# schematics.net
KiCad netlist of a schematic drawn in EasyEDA
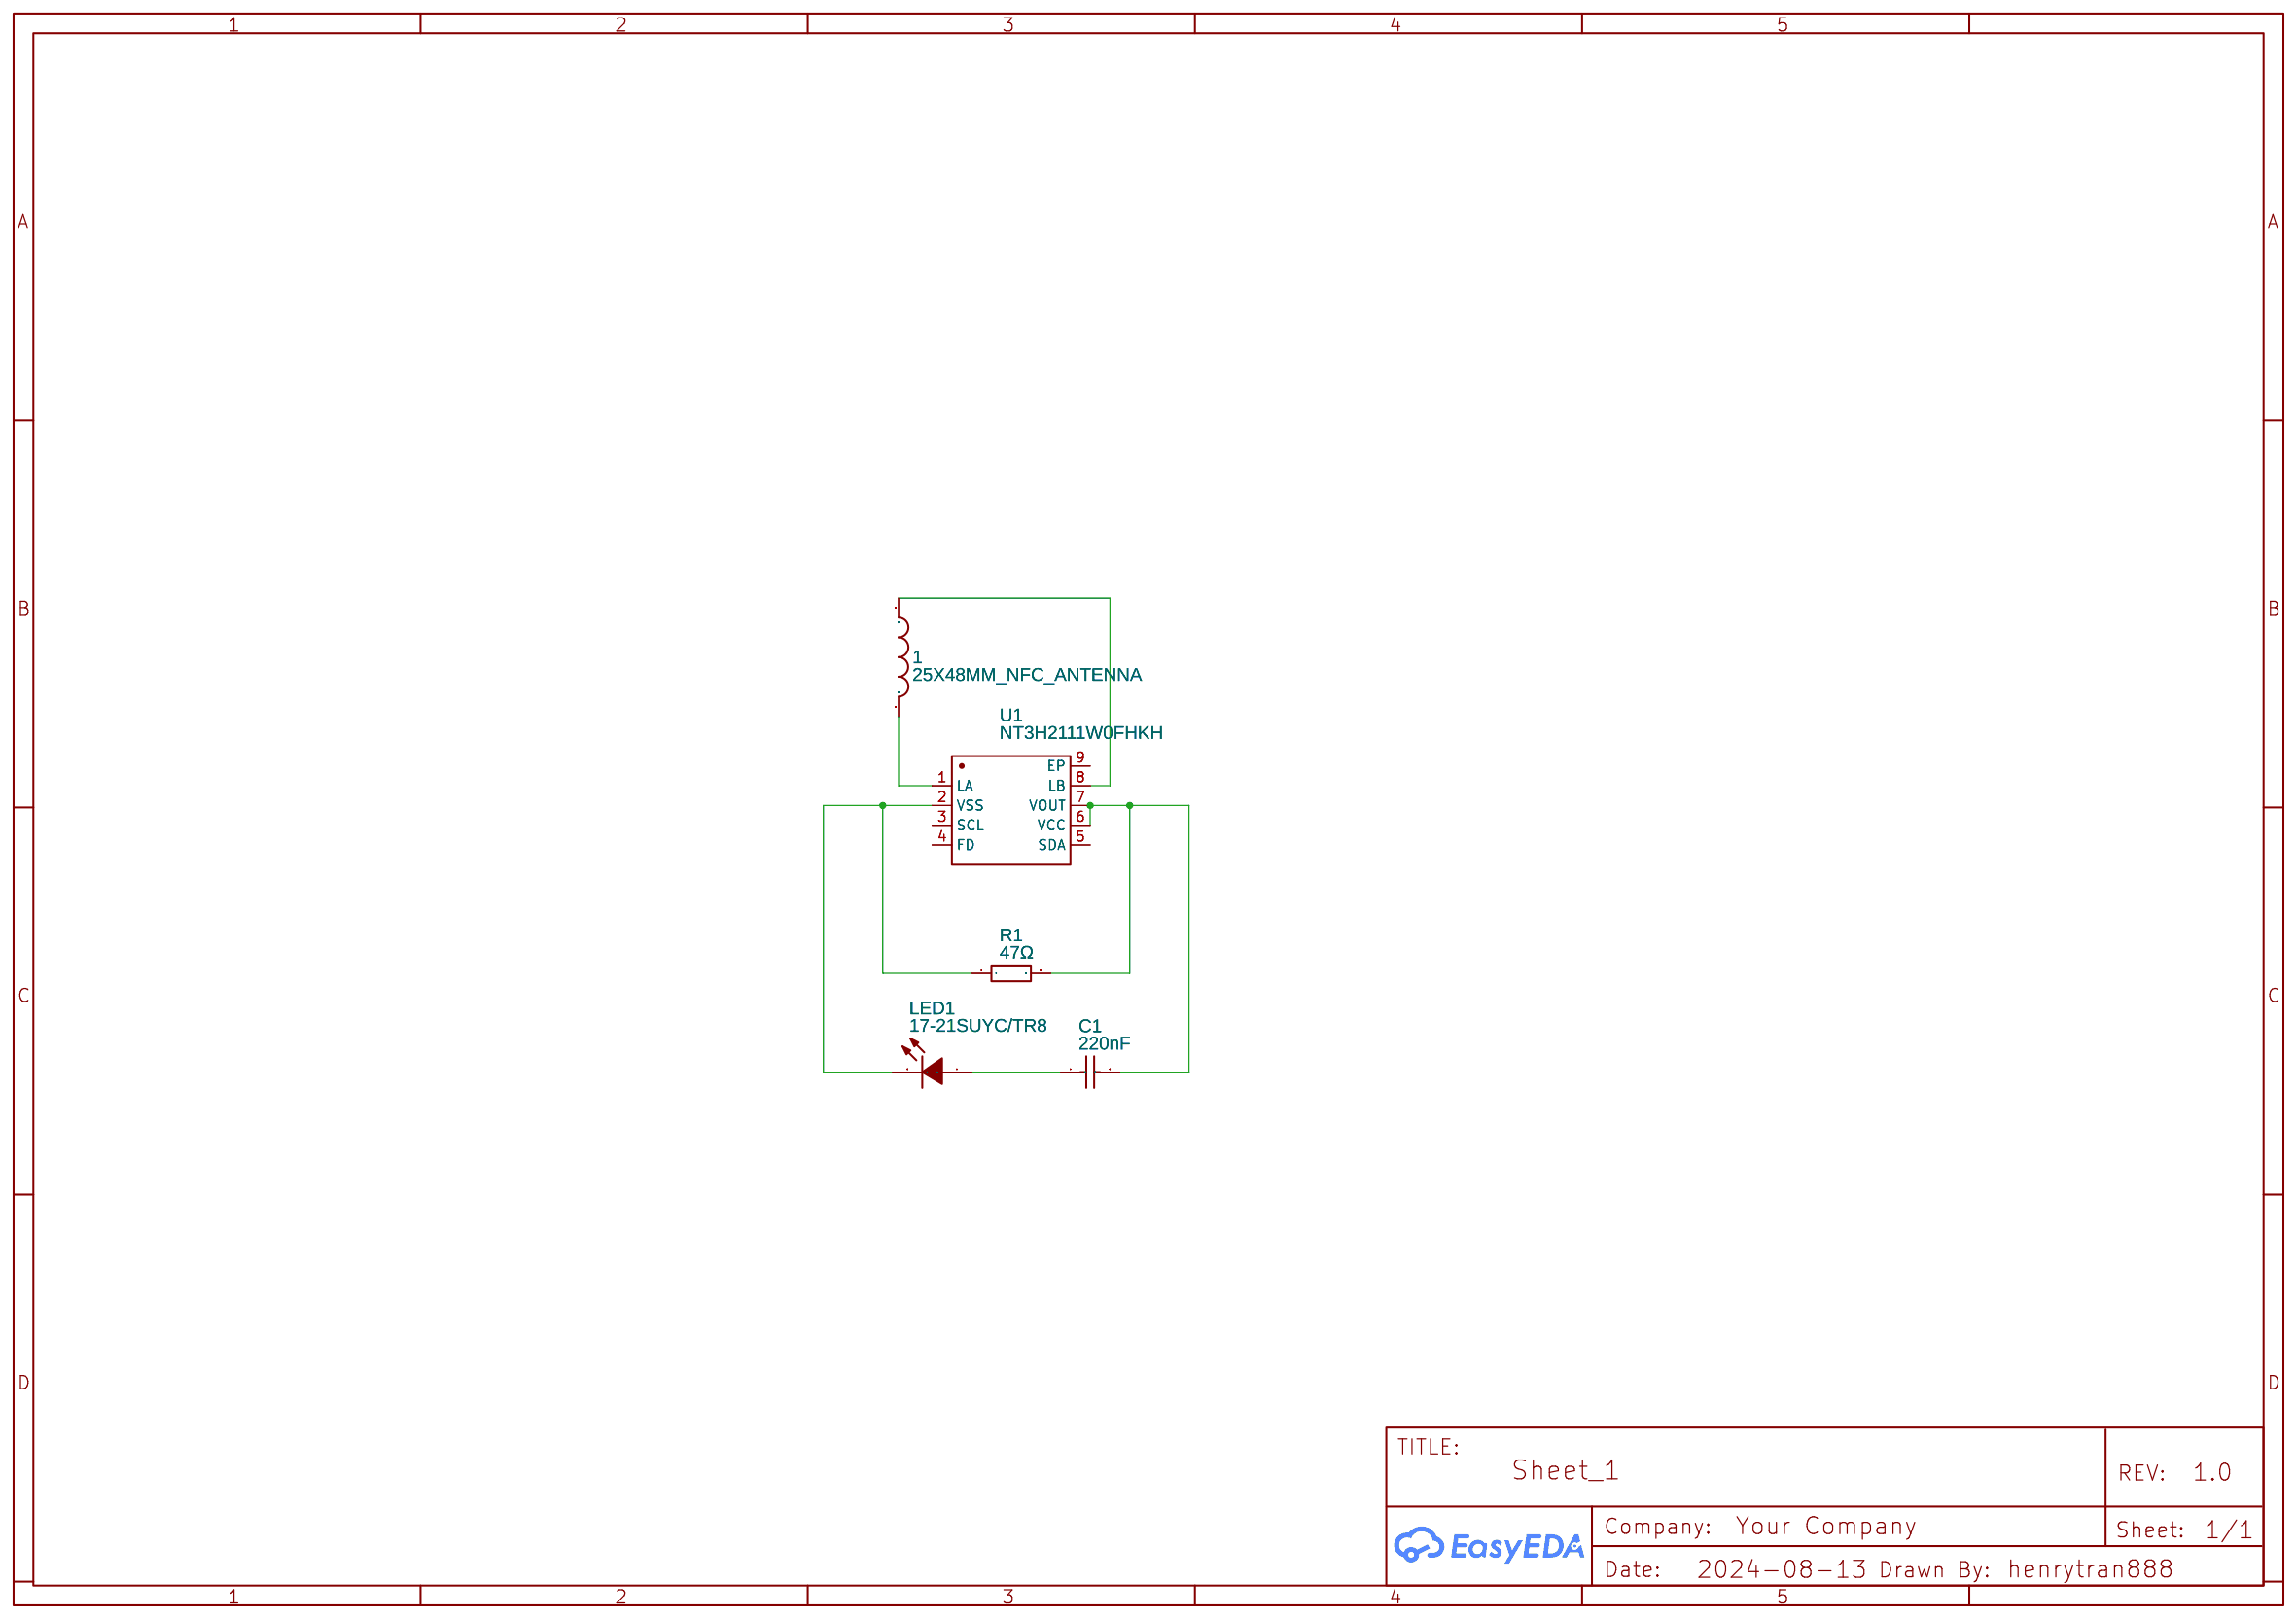
[diagram p0: schematic sheet]

(export (version "E")
  (design (tool "Eeschema 10.0.6"))
  (components
    (comp (ref "1") (value "25X48MM_NFC_ANTENNA") (libsource (lib "") (part "25X48MM_NFC_ANTENNA")))
    (comp (ref "C1")
      (value "220nF")
      (fields
        (field (name "Manufacturer Part") "CL10B224KA8NNNC")
        (field (name "Manufacturer") "SAMSUNG(三星)")
      )
      (libsource (lib "") (part "CL10B224KA8NNNC"))
    )
    (comp (ref "LED1")
      (value "17-21SUYC/TR8")
      (fields (field (name "Manufacturer Part") "KT-0805黄灯") (field (name "Manufacturer") "KENTO"))
      (libsource (lib "") (part "17-21SUYC/TR8"))
    )
    (comp (ref "R1")
      (value "47Ω")
      (fields
        (field (name "Manufacturer Part") "0603WAF470JT5E")
        (field (name "Manufacturer") "UNI-ROYAL(厚声)")
      )
      (libsource (lib "") (part "0603WAF470JT5E"))
    )
    (comp (ref "U1")
      (value "NT3H2111W0FHKH")
      (fields (field (name "Manufacturer") "NXP(恩智浦)"))
      (libsource (lib "") (part "NT3H2111W0FHKH"))
    )
  )
  (nets
    (net (code "1") (name "Net-(LED1-+)") (class "Default")
      (node (ref "C1") (pin "1") (pinfunction "1_1") (pintype "input"))
      (node (ref "LED1") (pin "1") (pinfunction "+_1") (pintype "unspecified"))
    )
    (net (code "2") (name "Net-(LED1--)") (class "Default")
      (node (ref "LED1") (pin "2") (pinfunction "-_2") (pintype "unspecified"))
      (node (ref "R1") (pin "1") (pinfunction "1_1") (pintype "input"))
      (node (ref "U1") (pin "2") (pinfunction "VSS_2") (pintype "unspecified"))
    )
    (net (code "3") (name "Net-(U1-LA)") (class "Default")
      (node (ref "1") (pin "P$2") (pinfunction "P$2_P$2") (pintype "bidirectional"))
      (node (ref "U1") (pin "1") (pinfunction "LA_1") (pintype "unspecified"))
    )
    (net (code "4") (name "Net-(U1-LB)") (class "Default")
      (node (ref "1") (pin "P$1") (pinfunction "P$1_P$1") (pintype "bidirectional"))
      (node (ref "U1") (pin "8") (pinfunction "LB_8") (pintype "unspecified"))
    )
    (net (code "5") (name "Net-(U1-VCC)") (class "Default")
      (node (ref "C1") (pin "2") (pinfunction "2_2") (pintype "input"))
      (node (ref "R1") (pin "2") (pinfunction "2_2") (pintype "input"))
      (node (ref "U1") (pin "6") (pinfunction "VCC_6") (pintype "unspecified"))
      (node (ref "U1") (pin "7") (pinfunction "VOUT_7") (pintype "unspecified"))
    )
    (net (code "6") (name "unconnected-(U1-EP-Pad9)") (class "Default")
      (node (ref "U1") (pin "9") (pinfunction "EP_9") (pintype "unspecified"))
    )
    (net (code "7") (name "unconnected-(U1-FD-Pad4)") (class "Default")
      (node (ref "U1") (pin "4") (pinfunction "FD_4") (pintype "unspecified"))
    )
    (net (code "8") (name "unconnected-(U1-SCL-Pad3)") (class "Default")
      (node (ref "U1") (pin "3") (pinfunction "SCL_3") (pintype "unspecified"))
    )
    (net (code "9") (name "unconnected-(U1-SDA-Pad5)") (class "Default")
      (node (ref "U1") (pin "5") (pinfunction "SDA_5") (pintype "unspecified"))
    )
  )
)
